# FM-Radio.net
KiCad netlist of a schematic drawn in EAGLE
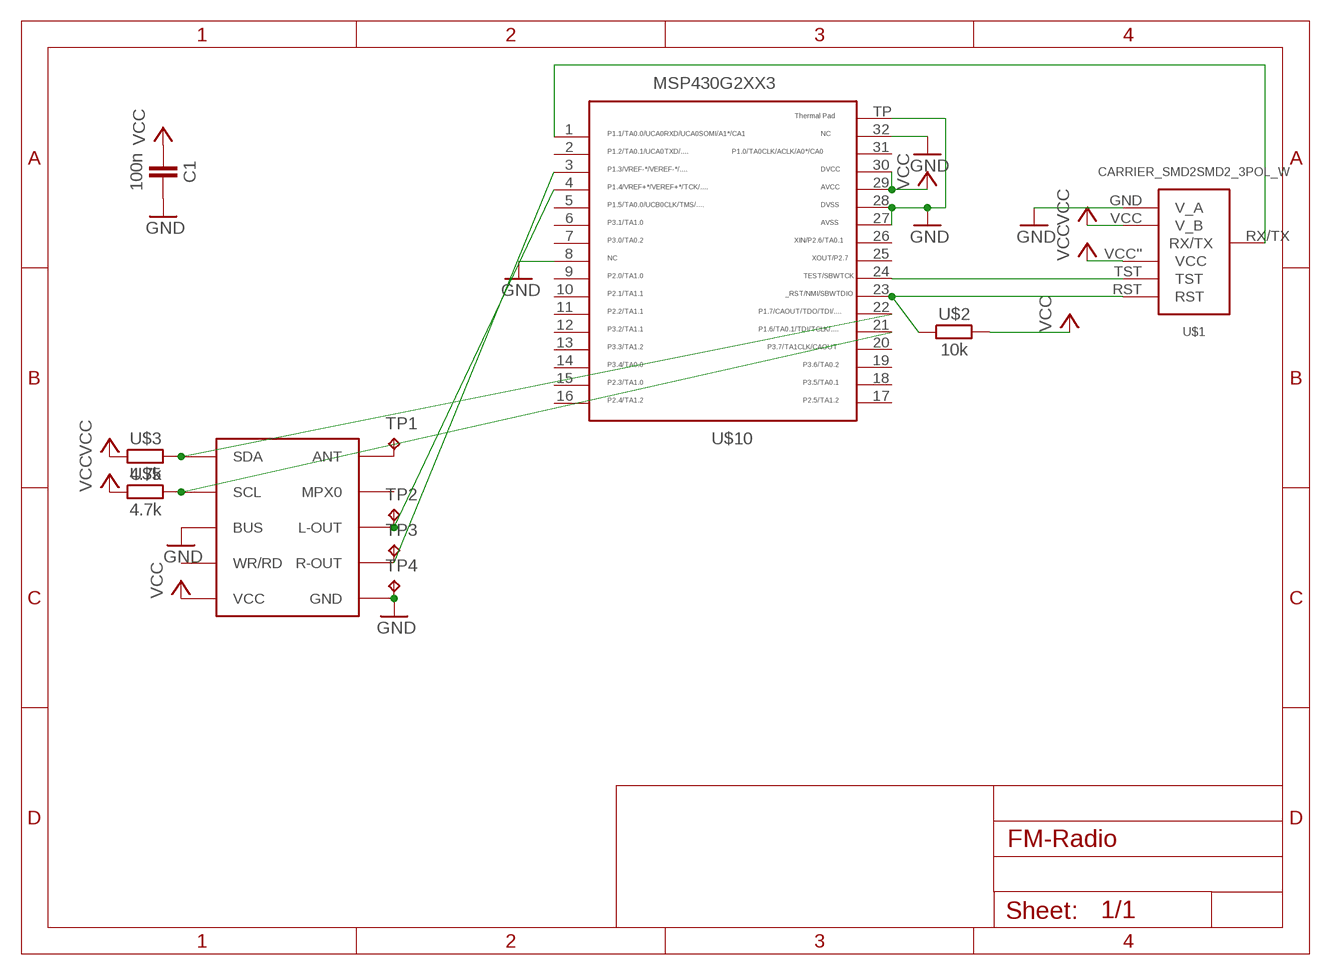
[diagram p0: schematic, sheet 1]

(export (version "E")
  (design (tool "Eeschema 10.0.6"))
  (components
    (comp (ref "C1")
      (value "100n")
      (footprint "eagle-import:603")
      (libsource (lib "eagle-import") (part "CAPACITOR"))
    )
    (comp (ref "TP1")
      (value "TPTP06R")
      (footprint "eagle-import:TP06R")
      (libsource (lib "eagle-import") (part "TPTP06R"))
    )
    (comp (ref "TP2")
      (value "TPTP06R")
      (footprint "eagle-import:TP06R")
      (libsource (lib "eagle-import") (part "TPTP06R"))
    )
    (comp (ref "TP3")
      (value "TPTP06R")
      (footprint "eagle-import:TP06R")
      (libsource (lib "eagle-import") (part "TPTP06R"))
    )
    (comp (ref "TP4")
      (value "TPTP06R")
      (footprint "eagle-import:TP06R")
      (libsource (lib "eagle-import") (part "TPTP06R"))
    )
    (comp (ref "U$1")
      (value "CARRIER_SMD2SMD2_3POL_W")
      (footprint "eagle-import:CARRIER_SMD2_WIDE_3POL")
      (libsource (lib "eagle-import") (part "CARRIER_SMD2SMD2_3POL_W"))
    )
    (comp (ref "U$2")
      (value "10k")
      (footprint "eagle-import:603")
      (libsource (lib "eagle-import") (part "RESISTOR0603"))
    )
    (comp (ref "U$3")
      (value "4.7k")
      (footprint "eagle-import:603")
      (libsource (lib "eagle-import") (part "RESISTOR0603"))
    )
    (comp (ref "U$4")
      (value "FM-RADIO")
      (footprint "eagle-import:FM-RADIO")
      (libsource (lib "eagle-import") (part "FM-RADIO"))
    )
    (comp (ref "U$5")
      (value "4.7k")
      (footprint "eagle-import:603")
      (libsource (lib "eagle-import") (part "RESISTOR0603"))
    )
    (comp (ref "U$10")
      (value "MSP430G2553")
      (footprint "eagle-import:QFN32")
      (libsource (lib "eagle-import") (part "MSP430G2553"))
    )
  )
  (nets
    (net (code "1") (name "GND") (class "Default")
      (node (ref "C1") (pin "2") (pinfunction "2_2") (pintype "passive"))
      (node (ref "TP4") (pin "TP") (pinfunction "TP_TP") (pintype "input"))
      (node (ref "U$1") (pin "GND") (pinfunction "V_A_GND") (pintype "bidirectional"))
      (node (ref "U$10") (pin "27") (pinfunction "27_27") (pintype "bidirectional"))
      (node (ref "U$10") (pin "28") (pinfunction "28_28") (pintype "bidirectional"))
      (node (ref "U$10") (pin "32") (pinfunction "32_32") (pintype "bidirectional"))
      (node (ref "U$10") (pin "8") (pinfunction "8_8") (pintype "bidirectional"))
      (node (ref "U$10") (pin "TP") (pinfunction "TP_TP") (pintype "bidirectional"))
      (node (ref "U$4") (pin "PAD3") (pinfunction "BUS_PAD3") (pintype "bidirectional"))
      (node (ref "U$4") (pin "PAD6") (pinfunction "GND_PAD6") (pintype "bidirectional"))
    )
    (net (code "2") (name "Net-(U$1-PadRST)") (class "Default")
      (node (ref "U$1") (pin "RST") (pinfunction "RST_RST") (pintype "bidirectional"))
      (node (ref "U$10") (pin "23") (pinfunction "23_23") (pintype "bidirectional"))
      (node (ref "U$2") (pin "1") (pinfunction "1_1") (pintype "passive"))
    )
    (net (code "3") (name "Net-(U$1-PadRX{slash}TX)") (class "Default")
      (node (ref "U$1") (pin "RX/TX") (pinfunction "RX/TX_RX/TX") (pintype "bidirectional"))
      (node (ref "U$10") (pin "1") (pinfunction "1_1") (pintype "bidirectional"))
    )
    (net (code "4") (name "Net-(U$1-PadTST)") (class "Default")
      (node (ref "U$1") (pin "TST") (pinfunction "TST_TST") (pintype "bidirectional"))
      (node (ref "U$10") (pin "24") (pinfunction "24_24") (pintype "bidirectional"))
    )
    (net (code "5") (name "Net-(U$4-ANT)") (class "Default")
      (node (ref "TP1") (pin "TP") (pinfunction "TP_TP") (pintype "input"))
      (node (ref "U$4") (pin "PAD11") (pinfunction "ANT_PAD11") (pintype "bidirectional"))
    )
    (net (code "6") (name "Net-(U$4-L-OUT)") (class "Default")
      (node (ref "TP2") (pin "TP") (pinfunction "TP_TP") (pintype "input"))
      (node (ref "U$10") (pin "4") (pinfunction "4_4") (pintype "bidirectional"))
      (node (ref "U$4") (pin "PAD9") (pinfunction "L-OUT_PAD9") (pintype "bidirectional"))
    )
    (net (code "7") (name "Net-(U$4-R-OUT)") (class "Default")
      (node (ref "TP3") (pin "TP") (pinfunction "TP_TP") (pintype "input"))
      (node (ref "U$10") (pin "3") (pinfunction "3_3") (pintype "bidirectional"))
      (node (ref "U$4") (pin "PAD7") (pinfunction "R-OUT_PAD7") (pintype "bidirectional"))
    )
    (net (code "8") (name "Net-(U$4-SCL)") (class "Default")
      (node (ref "U$10") (pin "21") (pinfunction "21_21") (pintype "bidirectional"))
      (node (ref "U$4") (pin "PAD2") (pinfunction "SCL_PAD2") (pintype "bidirectional"))
      (node (ref "U$5") (pin "2") (pinfunction "2_2") (pintype "passive"))
    )
    (net (code "9") (name "Net-(U$4-SDA)") (class "Default")
      (node (ref "U$10") (pin "22") (pinfunction "22_22") (pintype "bidirectional"))
      (node (ref "U$3") (pin "2") (pinfunction "2_2") (pintype "passive"))
      (node (ref "U$4") (pin "PAD1") (pinfunction "SDA_PAD1") (pintype "bidirectional"))
    )
    (net (code "10") (name "VCC") (class "Default")
      (node (ref "C1") (pin "1") (pinfunction "1_1") (pintype "passive"))
      (node (ref "U$1") (pin "VCC") (pinfunction "V_B_VCC") (pintype "bidirectional"))
      (node (ref "U$1") (pin "VCC''") (pinfunction "VCC_VCC''") (pintype "bidirectional"))
      (node (ref "U$10") (pin "29") (pinfunction "29_29") (pintype "bidirectional"))
      (node (ref "U$10") (pin "30") (pinfunction "30_30") (pintype "bidirectional"))
      (node (ref "U$2") (pin "2") (pinfunction "2_2") (pintype "passive"))
      (node (ref "U$3") (pin "1") (pinfunction "1_1") (pintype "passive"))
      (node (ref "U$4") (pin "PAD5") (pinfunction "VCC_PAD5") (pintype "bidirectional"))
      (node (ref "U$5") (pin "1") (pinfunction "1_1") (pintype "passive"))
    )
    (net (code "11") (name "unconnected-(U$4-MPX0-PadPAD10)") (class "Default")
      (node (ref "U$4") (pin "PAD10") (pinfunction "MPX0_PAD10") (pintype "bidirectional"))
    )
    (net (code "12") (name "unconnected-(U$4-WR{slash}RD-PadPAD4)") (class "Default")
      (node (ref "U$4") (pin "PAD4") (pinfunction "WR/RD_PAD4") (pintype "bidirectional"))
    )
    (net (code "13") (name "unconnected-(U$10-Pad2)") (class "Default")
      (node (ref "U$10") (pin "2") (pinfunction "2_2") (pintype "bidirectional"))
    )
    (net (code "14") (name "unconnected-(U$10-Pad5)") (class "Default")
      (node (ref "U$10") (pin "5") (pinfunction "5_5") (pintype "bidirectional"))
    )
    (net (code "15") (name "unconnected-(U$10-Pad6)") (class "Default")
      (node (ref "U$10") (pin "6") (pinfunction "6_6") (pintype "bidirectional"))
    )
    (net (code "16") (name "unconnected-(U$10-Pad7)") (class "Default")
      (node (ref "U$10") (pin "7") (pinfunction "7_7") (pintype "bidirectional"))
    )
    (net (code "17") (name "unconnected-(U$10-Pad9)") (class "Default")
      (node (ref "U$10") (pin "9") (pinfunction "9_9") (pintype "bidirectional"))
    )
    (net (code "18") (name "unconnected-(U$10-Pad10)") (class "Default")
      (node (ref "U$10") (pin "10") (pinfunction "10_10") (pintype "bidirectional"))
    )
    (net (code "19") (name "unconnected-(U$10-Pad11)") (class "Default")
      (node (ref "U$10") (pin "11") (pinfunction "11_11") (pintype "bidirectional"))
    )
    (net (code "20") (name "unconnected-(U$10-Pad12)") (class "Default")
      (node (ref "U$10") (pin "12") (pinfunction "12_12") (pintype "bidirectional"))
    )
    (net (code "21") (name "unconnected-(U$10-Pad13)") (class "Default")
      (node (ref "U$10") (pin "13") (pinfunction "13_13") (pintype "bidirectional"))
    )
    (net (code "22") (name "unconnected-(U$10-Pad14)") (class "Default")
      (node (ref "U$10") (pin "14") (pinfunction "14_14") (pintype "bidirectional"))
    )
    (net (code "23") (name "unconnected-(U$10-Pad15)") (class "Default")
      (node (ref "U$10") (pin "15") (pinfunction "15_15") (pintype "bidirectional"))
    )
    (net (code "24") (name "unconnected-(U$10-Pad16)") (class "Default")
      (node (ref "U$10") (pin "16") (pinfunction "16_16") (pintype "bidirectional"))
    )
    (net (code "25") (name "unconnected-(U$10-Pad17)") (class "Default")
      (node (ref "U$10") (pin "17") (pinfunction "17_17") (pintype "bidirectional"))
    )
    (net (code "26") (name "unconnected-(U$10-Pad18)") (class "Default")
      (node (ref "U$10") (pin "18") (pinfunction "18_18") (pintype "bidirectional"))
    )
    (net (code "27") (name "unconnected-(U$10-Pad19)") (class "Default")
      (node (ref "U$10") (pin "19") (pinfunction "19_19") (pintype "bidirectional"))
    )
    (net (code "28") (name "unconnected-(U$10-Pad20)") (class "Default")
      (node (ref "U$10") (pin "20") (pinfunction "20_20") (pintype "bidirectional"))
    )
    (net (code "29") (name "unconnected-(U$10-Pad25)") (class "Default")
      (node (ref "U$10") (pin "25") (pinfunction "25_25") (pintype "bidirectional"))
    )
    (net (code "30") (name "unconnected-(U$10-Pad26)") (class "Default")
      (node (ref "U$10") (pin "26") (pinfunction "26_26") (pintype "bidirectional"))
    )
    (net (code "31") (name "unconnected-(U$10-Pad31)") (class "Default")
      (node (ref "U$10") (pin "31") (pinfunction "31_31") (pintype "bidirectional"))
    )
  )
)
